# WAFC.net
KiCad netlist of a schematic drawn in Altium Designer
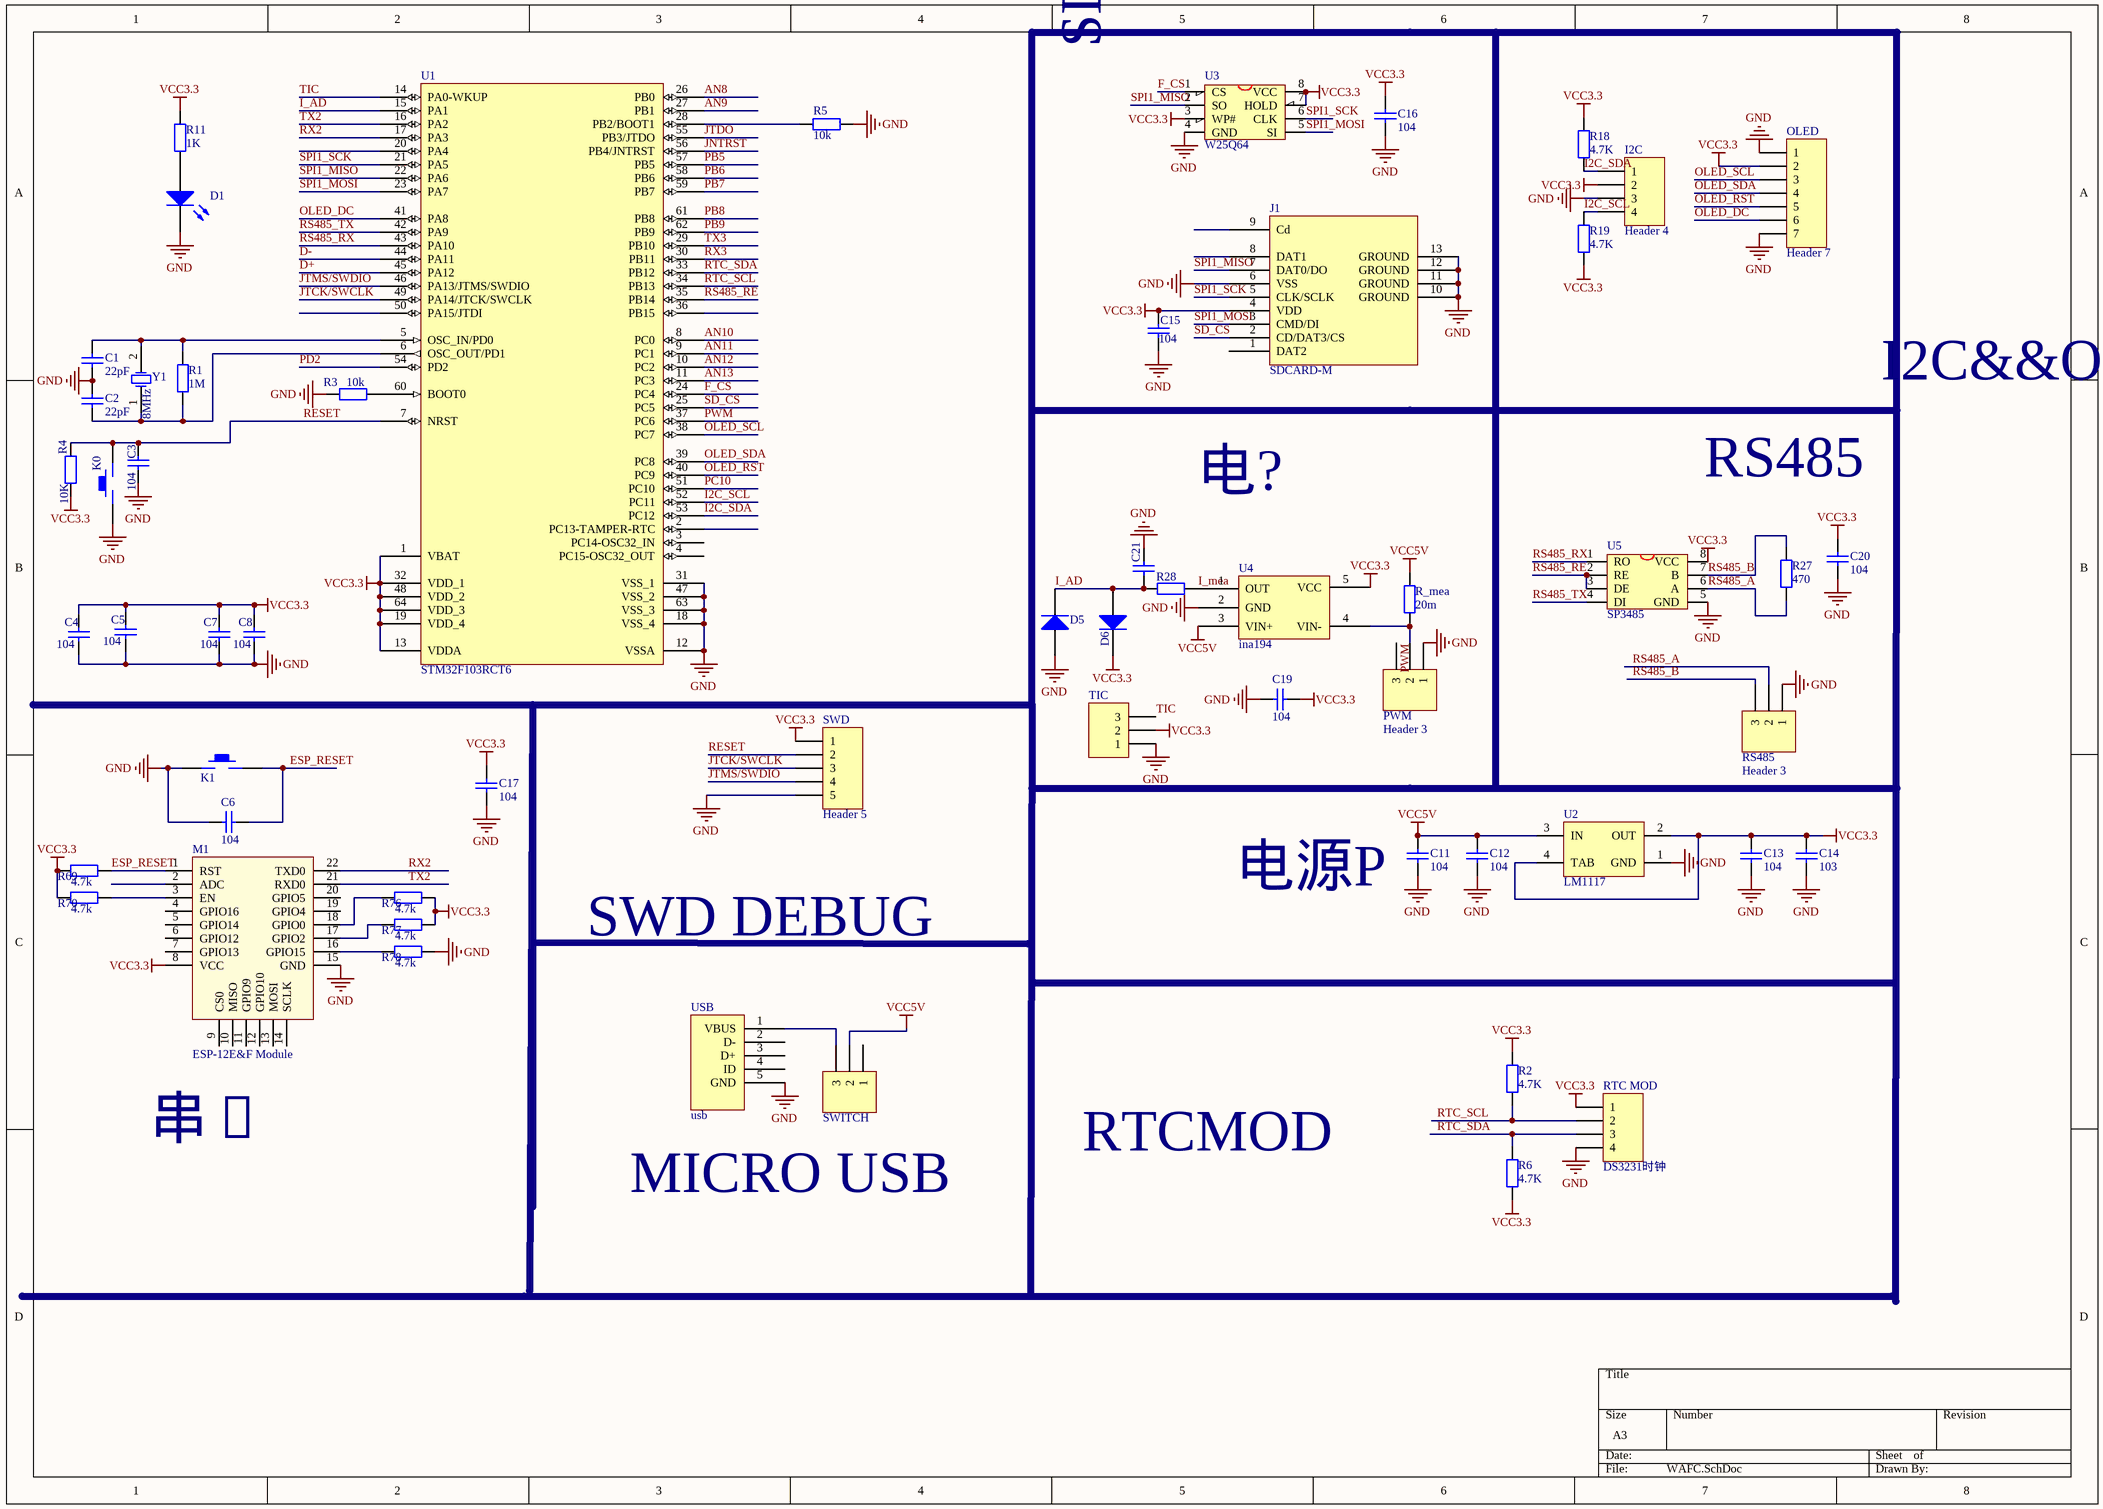
[diagram p0: WAFC.SchDoc]

(export (version "E")
  (design (tool "Eeschema 10.0.6"))
  (components
    (comp (ref "C1")
      (value "22pF")
      (footprint "0603")
      (description "Capacitor")
      (fields (field (name "Comment") "Cap") (field (name "PUBLISHER") "Altium Limited"))
      (libsource (lib "Miscellaneous Devices") (part "Cap"))
    )
    (comp (ref "C2")
      (value "22pF")
      (footprint "0603")
      (description "Capacitor")
      (fields (field (name "Comment") "Cap") (field (name "PUBLISHER") "Altium Limited"))
      (libsource (lib "Miscellaneous Devices") (part "Cap"))
    )
    (comp (ref "C3")
      (value "104")
      (footprint "0603")
      (description "Capacitor")
      (fields (field (name "Comment") "Cap") (field (name "PUBLISHER") "Altium Limited"))
      (libsource (lib "Miscellaneous Devices") (part "Cap"))
    )
    (comp (ref "C4")
      (value "104")
      (footprint "0603")
      (description "Capacitor")
      (fields (field (name "Comment") "Cap") (field (name "PUBLISHER") "Altium Limited"))
      (libsource (lib "Miscellaneous Devices") (part "Cap"))
    )
    (comp (ref "C5")
      (value "104")
      (footprint "0603")
      (description "Capacitor")
      (fields (field (name "Comment") "Cap") (field (name "PUBLISHER") "Altium Limited"))
      (libsource (lib "Miscellaneous Devices") (part "Cap"))
    )
    (comp (ref "C6")
      (value "104")
      (footprint "0603")
      (description "Capacitor")
      (fields (field (name "Comment") "Cap") (field (name "PUBLISHER") "Altium Limited"))
      (libsource (lib "Miscellaneous Devices") (part "Cap"))
    )
    (comp (ref "C7")
      (value "104")
      (footprint "0603")
      (description "Capacitor")
      (fields (field (name "Comment") "Cap") (field (name "PUBLISHER") "Altium Limited"))
      (libsource (lib "Miscellaneous Devices") (part "Cap"))
    )
    (comp (ref "C8")
      (value "104")
      (footprint "0603")
      (description "Capacitor")
      (fields (field (name "Comment") "Cap") (field (name "PUBLISHER") "Altium Limited"))
      (libsource (lib "Miscellaneous Devices") (part "Cap"))
    )
    (comp (ref "C11")
      (value "104")
      (footprint "0603")
      (description "Capacitor")
      (fields (field (name "Comment") "Cap") (field (name "PUBLISHER") "Altium Limited"))
      (libsource (lib "Miscellaneous Devices") (part "Cap"))
    )
    (comp (ref "C12")
      (value "104")
      (footprint "0603")
      (description "Capacitor")
      (fields (field (name "Comment") "Cap") (field (name "PUBLISHER") "Altium Limited"))
      (libsource (lib "Miscellaneous Devices") (part "Cap"))
    )
    (comp (ref "C13")
      (value "104")
      (footprint "0603")
      (description "Capacitor")
      (fields (field (name "Comment") "Cap") (field (name "PUBLISHER") "Altium Limited"))
      (libsource (lib "Miscellaneous Devices") (part "Cap"))
    )
    (comp (ref "C14")
      (value "103")
      (footprint "0603")
      (description "Capacitor")
      (fields (field (name "Comment") "Cap") (field (name "PUBLISHER") "Altium Limited"))
      (libsource (lib "Miscellaneous Devices") (part "Cap"))
    )
    (comp (ref "C15")
      (value "104")
      (footprint "0603")
      (description "Capacitor")
      (fields (field (name "Comment") "Cap") (field (name "PUBLISHER") "Altium Limited"))
      (libsource (lib "Miscellaneous Devices") (part "Cap"))
    )
    (comp (ref "C16")
      (value "104")
      (footprint "0603")
      (description "Capacitor")
      (fields (field (name "Comment") "Cap") (field (name "PUBLISHER") "Altium Limited"))
      (libsource (lib "Miscellaneous Devices") (part "Cap"))
    )
    (comp (ref "C17")
      (value "104")
      (footprint "0603")
      (description "Capacitor")
      (fields (field (name "Comment") "Cap") (field (name "PUBLISHER") "Altium Limited"))
      (libsource (lib "Miscellaneous Devices") (part "Cap"))
    )
    (comp (ref "C19")
      (value "104")
      (footprint "0603")
      (description "Capacitor")
      (fields (field (name "Comment") "Cap") (field (name "PUBLISHER") "Altium Limited"))
      (libsource (lib "Miscellaneous Devices") (part "Cap"))
    )
    (comp (ref "C20")
      (value "104")
      (footprint "0603")
      (description "Capacitor")
      (fields (field (name "Comment") "Cap") (field (name "PUBLISHER") "Altium Limited"))
      (libsource (lib "Miscellaneous Devices") (part "Cap"))
    )
    (comp (ref "C21")
      (value "Cap")
      (footprint "0603")
      (description "Capacitor")
      (fields (field (name "PUBLISHER") "Altium Limited"))
      (libsource (lib "Miscellaneous Devices") (part "Cap"))
    )
    (comp (ref "D1")
      (value "LED2")
      (footprint "0603")
      (description "Typical RED, GREEN, YELLOW, AMBER GaAs LED")
      (fields (field (name "PUBLISHER") "Altium Limited"))
      (libsource (lib "Miscellaneous Devices") (part "LED2"))
    )
    (comp (ref "D5")
      (value "SS14")
      (footprint "IN5819")
      (description "1 Amp General Purpose Rectifier")
      (fields (field (name "PUBLISHER") "Altium Limited"))
      (libsource (lib "Miscellaneous Devices") (part "Diode 1N4007"))
    )
    (comp (ref "D6")
      (value "SS14")
      (footprint "IN5819")
      (description "1 Amp General Purpose Rectifier")
      (fields (field (name "PUBLISHER") "Altium Limited"))
      (libsource (lib "Miscellaneous Devices") (part "Diode 1N4007"))
    )
    (comp (ref "I2C")
      (value "Header 4")
      (footprint "HDR1X4")
      (description "Header, 4-Pin")
      (fields (field (name "PUBLISHER") "Altium Limited"))
      (libsource (lib "Miscellaneous Connectors") (part "Header 4"))
    )
    (comp (ref "J1")
      (value "SDCARD-M")
      (footprint "SDCARD-M")
      (description "TF卡槽")
      (libsource (lib "MYLIB") (part "SDCARD-M"))
    )
    (comp (ref "K0") (value "K1") (footprint "sop2") (libsource (lib "") (part "KEY_1")))
    (comp (ref "K1") (value "K1") (footprint "sop2") (libsource (lib "MYLIB") (part "KEY")))
    (comp (ref "M1")
      (value "ESP-12E&F Module")
      (footprint "ESP-12E&F Module")
      (libsource (lib "ESP-12E&F Module") (part "ESP-12E&F Module"))
    )
    (comp (ref "OLED")
      (value "Header 7")
      (footprint "HDR1X7")
      (description "Header, 7-Pin")
      (fields (field (name "PUBLISHER") "Altium Limited"))
      (libsource (lib "Miscellaneous Connectors") (part "Header 7"))
    )
    (comp (ref "PWM")
      (value "Header 3")
      (footprint "HDR1X3")
      (description "Header, 3-Pin")
      (fields (field (name "PUBLISHER") "Altium Limited"))
      (libsource (lib "Miscellaneous Connectors") (part "Header 3"))
    )
    (comp (ref "R1")
      (value "1M")
      (footprint "0603")
      (description "Resistor")
      (fields (field (name "Comment") "Res2") (field (name "PUBLISHER") "Altium Limited"))
      (libsource (lib "Miscellaneous Devices") (part "Res2"))
    )
    (comp (ref "R2")
      (value "4.7K")
      (footprint "0603")
      (description "Resistor")
      (fields (field (name "Comment") "Res2") (field (name "PUBLISHER") "Altium Limited"))
      (libsource (lib "") (part "Res2_2"))
    )
    (comp (ref "R3")
      (value "10k")
      (footprint "0603")
      (description "Resistor")
      (fields (field (name "Comment") "Res2") (field (name "PUBLISHER") "Altium Limited"))
      (libsource (lib "") (part "Res2_1"))
    )
    (comp (ref "R4")
      (value "10K")
      (footprint "0603")
      (description "Resistor")
      (fields (field (name "Comment") "Res2") (field (name "PUBLISHER") "Altium Limited"))
      (libsource (lib "Miscellaneous Devices") (part "Res2"))
    )
    (comp (ref "R5")
      (value "10k")
      (footprint "0603")
      (description "Resistor")
      (fields (field (name "Comment") "Res2") (field (name "PUBLISHER") "Altium Limited"))
      (libsource (lib "") (part "Res2_1"))
    )
    (comp (ref "R6")
      (value "4.7K")
      (footprint "0603")
      (description "Resistor")
      (fields (field (name "Comment") "Res2") (field (name "PUBLISHER") "Altium Limited"))
      (libsource (lib "") (part "Res2_2"))
    )
    (comp (ref "R11")
      (value "1K")
      (footprint "0603")
      (description "Resistor")
      (fields (field (name "Comment") "Res2") (field (name "PUBLISHER") "Altium Limited"))
      (libsource (lib "Miscellaneous Devices") (part "Res2"))
    )
    (comp (ref "R18")
      (value "4.7K")
      (footprint "0603")
      (description "Resistor")
      (fields (field (name "Comment") "Res2") (field (name "PUBLISHER") "Altium Limited"))
      (libsource (lib "") (part "Res2_2"))
    )
    (comp (ref "R19")
      (value "4.7K")
      (footprint "0603")
      (description "Resistor")
      (fields (field (name "Comment") "Res2") (field (name "PUBLISHER") "Altium Limited"))
      (libsource (lib "") (part "Res2_2"))
    )
    (comp (ref "R27")
      (value "470")
      (footprint "0603")
      (description "Resistor")
      (fields (field (name "Comment") "Res2") (field (name "PUBLISHER") "Altium Limited"))
      (libsource (lib "") (part "Res2_2"))
    )
    (comp (ref "R28")
      (value "Res2")
      (footprint "0603")
      (description "Resistor")
      (fields (field (name "PUBLISHER") "Altium Limited"))
      (libsource (lib "") (part "Res2_3"))
    )
    (comp (ref "R69")
      (value "4.7k")
      (footprint "0603")
      (fields (field (name "Comment") "Res2"))
      (libsource (lib "S1") (part "RES"))
    )
    (comp (ref "R70")
      (value "4.7k")
      (footprint "0603")
      (fields (field (name "Comment") "Res2"))
      (libsource (lib "S1") (part "RES"))
    )
    (comp (ref "R76")
      (value "4.7k")
      (footprint "0603")
      (fields (field (name "Comment") "Res2"))
      (libsource (lib "S1") (part "RES"))
    )
    (comp (ref "R77")
      (value "4.7k")
      (footprint "0603")
      (fields (field (name "Comment") "Res2"))
      (libsource (lib "S1") (part "RES"))
    )
    (comp (ref "R78")
      (value "4.7k")
      (footprint "0603")
      (fields (field (name "Comment") "Res2"))
      (libsource (lib "S1") (part "RES"))
    )
    (comp (ref "RS485")
      (value "Header 3")
      (footprint "DZ3*3.5")
      (description "Header, 3-Pin")
      (fields (field (name "PUBLISHER") "Altium Limited"))
      (libsource (lib "Miscellaneous Connectors") (part "Header 3"))
    )
    (comp (ref "RTC MOD")
      (value "DS3231时钟")
      (footprint "HDR1X4")
      (description "Header, 4-Pin")
      (fields (field (name "PUBLISHER") "Altium Limited"))
      (libsource (lib "Miscellaneous Connectors") (part "Header 4"))
    )
    (comp (ref "R_mea")
      (value "20m")
      (footprint "0805")
      (description "Resistor")
      (fields (field (name "Comment") "Res2") (field (name "PUBLISHER") "Altium Limited"))
      (libsource (lib "Miscellaneous Devices") (part "Res2"))
    )
    (comp (ref "SWD")
      (value "Header 5")
      (footprint "HDR1X5")
      (description "Header, 5-Pin")
      (fields (field (name "PUBLISHER") "Altium Limited"))
      (libsource (lib "Miscellaneous Connectors") (part "Header 5"))
    )
    (comp (ref "SWITCH")
      (value "Header 3")
      (footprint "12D00")
      (description "Header, 3-Pin")
      (fields (field (name "PUBLISHER") "Altium Limited"))
      (libsource (lib "Miscellaneous Connectors") (part "Header 3"))
    )
    (comp (ref "TIC")
      (value "Header 3")
      (footprint "DZ3*3.5")
      (description "Header, 3-Pin")
      (fields (field (name "PUBLISHER") "Altium Limited"))
      (libsource (lib "") (part "Header 3_1"))
    )
    (comp (ref "U1")
      (value "STM32F103RCT6")
      (footprint "LQFP64")
      (description "STM32 ARM-based 32-bit MCU with 128 Kbytes Flash, 64-pin LQFP, Industrial Temperature")
      (fields (field (name "PUBLISHER") "Altium Limited"))
      (libsource (lib "MYLIB") (part "STM32F103RBT6"))
    )
    (comp (ref "U2")
      (value "LM1117")
      (footprint "MP04A_N")
      (description "800mA LDO")
      (fields
        (field (name "PARTNUMBER") "LM1117IMP-5.0")
        (field (name "MANUFACTURER") "National Semiconductor")
        (field (name "PUBLISHER") "Altium Limited")
      )
      (libsource (lib "MYLIB") (part "LM1117"))
    )
    (comp (ref "U3")
      (value "W25Q64")
      (footprint "SOIC-8")
      (description "W25X16;SST25VF016;MX25L1605")
      (libsource (lib "WARSHIP") (part "W25X16"))
    )
    (comp (ref "U4") (value "ina194") (footprint "ina194") (libsource (lib "MYLIB") (part "ina194")))
    (comp (ref "U5") (value "SP3485") (footprint "SOP-8") (libsource (lib "WARSHIP") (part "MAX3485")))
    (comp (ref "USB") (value "usb") (libsource (lib "xljc") (part "usb")))
    (comp (ref "Y1")
      (value "8MHz")
      (footprint "XTAL_US")
      (description "Crystal Oscillator")
      (fields (field (name "PUBLISHER") "Altium Limited"))
      (libsource (lib "WARSHIP") (part "XTAL"))
    )
  )
  (nets
    (net (code "1") (name "/AN8") (class "Default")
      (node (ref "U1") (pin "26") (pinfunction "PB0_26") (pintype "bidirectional"))
    )
    (net (code "2") (name "/AN9") (class "Default")
      (node (ref "U1") (pin "27") (pinfunction "PB1_27") (pintype "bidirectional"))
    )
    (net (code "3") (name "/AN10") (class "Default")
      (node (ref "U1") (pin "8") (pinfunction "PC0_8") (pintype "bidirectional"))
    )
    (net (code "4") (name "/AN11") (class "Default")
      (node (ref "U1") (pin "9") (pinfunction "PC1_9") (pintype "bidirectional"))
    )
    (net (code "5") (name "/AN12") (class "Default")
      (node (ref "U1") (pin "10") (pinfunction "PC2_10") (pintype "bidirectional"))
    )
    (net (code "6") (name "/AN13") (class "Default")
      (node (ref "U1") (pin "11") (pinfunction "PC3_11") (pintype "bidirectional"))
    )
    (net (code "7") (name "/D+") (class "Default")
      (node (ref "U1") (pin "45") (pinfunction "PA12_45") (pintype "bidirectional"))
    )
    (net (code "8") (name "/D-") (class "Default")
      (node (ref "U1") (pin "44") (pinfunction "PA11_44") (pintype "bidirectional"))
    )
    (net (code "9") (name "/ESP_RESET") (class "Default")
      (node (ref "C6") (pin "1") (pinfunction "1_1") (pintype "passive"))
      (node (ref "K1") (pin "2") (pinfunction "2_2") (pintype "passive"))
      (node (ref "M1") (pin "1") (pinfunction "RST_1") (pintype "passive"))
      (node (ref "R69") (pin "1") (pinfunction "1_1") (pintype "passive"))
    )
    (net (code "10") (name "/F_CS") (class "Default")
      (node (ref "U1") (pin "24") (pinfunction "PC4_24") (pintype "bidirectional"))
      (node (ref "U3") (pin "1") (pinfunction "CS_1") (pintype "passive"))
    )
    (net (code "11") (name "/I2C_SCL") (class "Default")
      (node (ref "I2C") (pin "4") (pinfunction "4_4") (pintype "passive"))
      (node (ref "R19") (pin "1") (pinfunction "1_1") (pintype "passive"))
      (node (ref "U1") (pin "52") (pinfunction "PC11_52") (pintype "bidirectional"))
    )
    (net (code "12") (name "/I2C_SDA") (class "Default")
      (node (ref "I2C") (pin "1") (pinfunction "1_1") (pintype "passive"))
      (node (ref "R18") (pin "2") (pinfunction "2_2") (pintype "passive"))
      (node (ref "U1") (pin "53") (pinfunction "PC12_53") (pintype "bidirectional"))
    )
    (net (code "13") (name "/I_AD") (class "Default")
      (node (ref "C21") (pin "1") (pinfunction "1_1") (pintype "passive"))
      (node (ref "D5") (pin "2") (pinfunction "K_2") (pintype "passive"))
      (node (ref "D6") (pin "1") (pinfunction "A_1") (pintype "passive"))
      (node (ref "R28") (pin "1") (pinfunction "1_1") (pintype "passive"))
      (node (ref "U1") (pin "15") (pinfunction "PA1_15") (pintype "bidirectional"))
    )
    (net (code "14") (name "/I_mea") (class "Default")
      (node (ref "R28") (pin "2") (pinfunction "2_2") (pintype "passive"))
      (node (ref "U4") (pin "1") (pinfunction "OUT_1") (pintype "passive"))
    )
    (net (code "15") (name "/JNTRST") (class "Default")
      (node (ref "U1") (pin "56") (pinfunction "PB4/JNTRST_56") (pintype "bidirectional"))
    )
    (net (code "16") (name "/JTCK{slash}SWCLK") (class "Default")
      (node (ref "SWD") (pin "3") (pinfunction "3_3") (pintype "passive"))
      (node (ref "U1") (pin "49") (pinfunction "PA14/JTCK/SWCLK_49") (pintype "bidirectional"))
    )
    (net (code "17") (name "/JTDO") (class "Default")
      (node (ref "U1") (pin "55") (pinfunction "PB3/JTDO_55") (pintype "bidirectional"))
    )
    (net (code "18") (name "/JTMS{slash}SWDIO") (class "Default")
      (node (ref "SWD") (pin "4") (pinfunction "4_4") (pintype "passive"))
      (node (ref "U1") (pin "46") (pinfunction "PA13/JTMS/SWDIO_46") (pintype "bidirectional"))
    )
    (net (code "19") (name "/OLED_DC") (class "Default")
      (node (ref "OLED") (pin "6") (pinfunction "6_6") (pintype "passive"))
      (node (ref "U1") (pin "41") (pinfunction "PA8_41") (pintype "bidirectional"))
    )
    (net (code "20") (name "/OLED_RST") (class "Default")
      (node (ref "OLED") (pin "5") (pinfunction "5_5") (pintype "passive"))
      (node (ref "U1") (pin "40") (pinfunction "PC9_40") (pintype "bidirectional"))
    )
    (net (code "21") (name "/OLED_SCL") (class "Default")
      (node (ref "OLED") (pin "3") (pinfunction "3_3") (pintype "passive"))
      (node (ref "U1") (pin "38") (pinfunction "PC7_38") (pintype "bidirectional"))
    )
    (net (code "22") (name "/OLED_SDA") (class "Default")
      (node (ref "OLED") (pin "4") (pinfunction "4_4") (pintype "passive"))
      (node (ref "U1") (pin "39") (pinfunction "PC8_39") (pintype "bidirectional"))
    )
    (net (code "23") (name "/PB5") (class "Default")
      (node (ref "U1") (pin "57") (pinfunction "PB5_57") (pintype "bidirectional"))
    )
    (net (code "24") (name "/PB6") (class "Default")
      (node (ref "U1") (pin "58") (pinfunction "PB6_58") (pintype "bidirectional"))
    )
    (net (code "25") (name "/PB7") (class "Default")
      (node (ref "U1") (pin "59") (pinfunction "PB7_59") (pintype "bidirectional"))
    )
    (net (code "26") (name "/PB8") (class "Default")
      (node (ref "U1") (pin "61") (pinfunction "PB8_61") (pintype "bidirectional"))
    )
    (net (code "27") (name "/PB9") (class "Default")
      (node (ref "U1") (pin "62") (pinfunction "PB9_62") (pintype "bidirectional"))
    )
    (net (code "28") (name "/PC10") (class "Default")
      (node (ref "U1") (pin "51") (pinfunction "PC10_51") (pintype "bidirectional"))
    )
    (net (code "29") (name "/PD2") (class "Default")
      (node (ref "U1") (pin "54") (pinfunction "PD2_54") (pintype "bidirectional"))
    )
    (net (code "30") (name "/PWM") (class "Default")
      (node (ref "PWM") (pin "3") (pinfunction "3_3") (pintype "passive"))
      (node (ref "U1") (pin "37") (pinfunction "PC6_37") (pintype "bidirectional"))
    )
    (net (code "31") (name "/RESET") (class "Default")
      (node (ref "C3") (pin "2") (pinfunction "2_2") (pintype "passive"))
      (node (ref "K0") (pin "2") (pinfunction "2_2") (pintype "passive"))
      (node (ref "R4") (pin "2") (pinfunction "2_2") (pintype "passive"))
      (node (ref "SWD") (pin "2") (pinfunction "2_2") (pintype "passive"))
      (node (ref "U1") (pin "7") (pinfunction "NRST_7") (pintype "bidirectional"))
    )
    (net (code "32") (name "/RS485_A") (class "Default")
      (node (ref "R27") (pin "2") (pinfunction "2_2") (pintype "passive"))
      (node (ref "RS485") (pin "2") (pinfunction "2_2") (pintype "passive"))
      (node (ref "U5") (pin "6") (pinfunction "A_6") (pintype "passive"))
    )
    (net (code "33") (name "/RS485_B") (class "Default")
      (node (ref "R27") (pin "1") (pinfunction "1_1") (pintype "passive"))
      (node (ref "RS485") (pin "3") (pinfunction "3_3") (pintype "passive"))
      (node (ref "U5") (pin "7") (pinfunction "B_7") (pintype "passive"))
    )
    (net (code "34") (name "/RS485_RE") (class "Default")
      (node (ref "U1") (pin "35") (pinfunction "PB14_35") (pintype "bidirectional"))
      (node (ref "U5") (pin "2") (pinfunction "RE_2") (pintype "passive"))
      (node (ref "U5") (pin "3") (pinfunction "DE_3") (pintype "passive"))
    )
    (net (code "35") (name "/RS485_RX") (class "Default")
      (node (ref "U1") (pin "43") (pinfunction "PA10_43") (pintype "bidirectional"))
      (node (ref "U5") (pin "1") (pinfunction "RO_1") (pintype "passive"))
    )
    (net (code "36") (name "/RS485_TX") (class "Default")
      (node (ref "U1") (pin "42") (pinfunction "PA9_42") (pintype "bidirectional"))
      (node (ref "U5") (pin "4") (pinfunction "DI_4") (pintype "passive"))
    )
    (net (code "37") (name "/RTC_SCL") (class "Default")
      (node (ref "R2") (pin "2") (pinfunction "2_2") (pintype "passive"))
      (node (ref "RTC MOD") (pin "2") (pinfunction "2_2") (pintype "passive"))
      (node (ref "U1") (pin "34") (pinfunction "PB13_34") (pintype "bidirectional"))
    )
    (net (code "38") (name "/RTC_SDA") (class "Default")
      (node (ref "R6") (pin "1") (pinfunction "1_1") (pintype "passive"))
      (node (ref "RTC MOD") (pin "3") (pinfunction "3_3") (pintype "passive"))
      (node (ref "U1") (pin "33") (pinfunction "PB12_33") (pintype "bidirectional"))
    )
    (net (code "39") (name "/RX2") (class "Default")
      (node (ref "M1") (pin "22") (pinfunction "TXD0_22") (pintype "passive"))
      (node (ref "U1") (pin "17") (pinfunction "PA3_17") (pintype "bidirectional"))
    )
    (net (code "40") (name "/RX3") (class "Default")
      (node (ref "U1") (pin "30") (pinfunction "PB11_30") (pintype "bidirectional"))
    )
    (net (code "41") (name "/SD_CS") (class "Default")
      (node (ref "J1") (pin "2") (pinfunction "CD/DAT3/CS_2") (pintype "passive"))
      (node (ref "U1") (pin "25") (pinfunction "PC5_25") (pintype "bidirectional"))
    )
    (net (code "42") (name "/SPI1_MISO") (class "Default")
      (node (ref "J1") (pin "7") (pinfunction "DAT0/DO_7") (pintype "passive"))
      (node (ref "U1") (pin "22") (pinfunction "PA6_22") (pintype "bidirectional"))
      (node (ref "U3") (pin "2") (pinfunction "SO_2") (pintype "passive"))
    )
    (net (code "43") (name "/SPI1_MOSI") (class "Default")
      (node (ref "J1") (pin "3") (pinfunction "CMD/DI_3") (pintype "passive"))
      (node (ref "U1") (pin "23") (pinfunction "PA7_23") (pintype "bidirectional"))
      (node (ref "U3") (pin "5") (pinfunction "SI_5") (pintype "passive"))
    )
    (net (code "44") (name "/SPI1_SCK") (class "Default")
      (node (ref "J1") (pin "5") (pinfunction "CLK/SCLK_5") (pintype "passive"))
      (node (ref "U1") (pin "21") (pinfunction "PA5_21") (pintype "bidirectional"))
      (node (ref "U3") (pin "6") (pinfunction "CLK_6") (pintype "passive"))
    )
    (net (code "45") (name "/TIC") (class "Default")
      (node (ref "TIC") (pin "3") (pinfunction "3_3") (pintype "passive"))
      (node (ref "U1") (pin "14") (pinfunction "PA0-WKUP_14") (pintype "bidirectional"))
    )
    (net (code "46") (name "/TX2") (class "Default")
      (node (ref "M1") (pin "21") (pinfunction "RXD0_21") (pintype "passive"))
      (node (ref "U1") (pin "16") (pinfunction "PA2_16") (pintype "bidirectional"))
    )
    (net (code "47") (name "/TX3") (class "Default")
      (node (ref "U1") (pin "29") (pinfunction "PB10_29") (pintype "bidirectional"))
    )
    (net (code "48") (name "GND") (class "Default")
      (node (ref "C1") (pin "1") (pinfunction "1_1") (pintype "passive"))
      (node (ref "C11") (pin "1") (pinfunction "1_1") (pintype "passive"))
      (node (ref "C12") (pin "1") (pinfunction "1_1") (pintype "passive"))
      (node (ref "C13") (pin "1") (pinfunction "1_1") (pintype "passive"))
      (node (ref "C14") (pin "1") (pinfunction "1_1") (pintype "passive"))
      (node (ref "C15") (pin "1") (pinfunction "1_1") (pintype "passive"))
      (node (ref "C16") (pin "1") (pinfunction "1_1") (pintype "passive"))
      (node (ref "C17") (pin "1") (pinfunction "1_1") (pintype "passive"))
      (node (ref "C19") (pin "1") (pinfunction "1_1") (pintype "passive"))
      (node (ref "C2") (pin "2") (pinfunction "2_2") (pintype "passive"))
      (node (ref "C20") (pin "1") (pinfunction "1_1") (pintype "passive"))
      (node (ref "C21") (pin "2") (pinfunction "2_2") (pintype "passive"))
      (node (ref "C3") (pin "1") (pinfunction "1_1") (pintype "passive"))
      (node (ref "C4") (pin "2") (pinfunction "2_2") (pintype "passive"))
      (node (ref "C5") (pin "2") (pinfunction "2_2") (pintype "passive"))
      (node (ref "C6") (pin "2") (pinfunction "2_2") (pintype "passive"))
      (node (ref "C7") (pin "2") (pinfunction "2_2") (pintype "passive"))
      (node (ref "C8") (pin "2") (pinfunction "2_2") (pintype "passive"))
      (node (ref "D1") (pin "2") (pinfunction "K_2") (pintype "passive"))
      (node (ref "D5") (pin "1") (pinfunction "A_1") (pintype "passive"))
      (node (ref "I2C") (pin "3") (pinfunction "3_3") (pintype "passive"))
      (node (ref "J1") (pin "10") (pinfunction "GROUND_10") (pintype "passive"))
      (node (ref "J1") (pin "11") (pinfunction "GROUND_11") (pintype "passive"))
      (node (ref "J1") (pin "12") (pinfunction "GROUND_12") (pintype "passive"))
      (node (ref "J1") (pin "13") (pinfunction "GROUND_13") (pintype "passive"))
      (node (ref "J1") (pin "6") (pinfunction "VSS_6") (pintype "passive"))
      (node (ref "K0") (pin "1") (pinfunction "1_1") (pintype "passive"))
      (node (ref "K1") (pin "1") (pinfunction "1_1") (pintype "passive"))
      (node (ref "M1") (pin "15") (pinfunction "GND_15") (pintype "passive"))
      (node (ref "OLED") (pin "1") (pinfunction "1_1") (pintype "passive"))
      (node (ref "OLED") (pin "7") (pinfunction "7_7") (pintype "passive"))
      (node (ref "PWM") (pin "1") (pinfunction "1_1") (pintype "passive"))
      (node (ref "R3") (pin "2") (pinfunction "2_2") (pintype "passive"))
      (node (ref "R5") (pin "1") (pinfunction "1_1") (pintype "passive"))
      (node (ref "R78") (pin "1") (pinfunction "1_1") (pintype "passive"))
      (node (ref "RS485") (pin "1") (pinfunction "1_1") (pintype "passive"))
      (node (ref "RTC MOD") (pin "4") (pinfunction "4_4") (pintype "passive"))
      (node (ref "SWD") (pin "5") (pinfunction "5_5") (pintype "passive"))
      (node (ref "TIC") (pin "1") (pinfunction "1_1") (pintype "passive"))
      (node (ref "U1") (pin "12") (pinfunction "VSSA_12") (pintype "power_in"))
      (node (ref "U1") (pin "18") (pinfunction "VSS_4_18") (pintype "power_in"))
      (node (ref "U1") (pin "31") (pinfunction "VSS_1_31") (pintype "power_in"))
      (node (ref "U1") (pin "47") (pinfunction "VSS_2_47") (pintype "power_in"))
      (node (ref "U1") (pin "63") (pinfunction "VSS_3_63") (pintype "power_in"))
      (node (ref "U2") (pin "1") (pinfunction "GND_1") (pintype "power_in"))
      (node (ref "U3") (pin "4") (pinfunction "GND_4") (pintype "passive"))
      (node (ref "U4") (pin "2") (pinfunction "GND_2") (pintype "passive"))
      (node (ref "U5") (pin "5") (pinfunction "GND_5") (pintype "passive"))
      (node (ref "USB") (pin "5") (pinfunction "GND_5") (pintype "passive"))
    )
    (net (code "49") (name "Net-(D1-A)") (class "Default")
      (node (ref "D1") (pin "1") (pinfunction "A_1") (pintype "passive"))
      (node (ref "R11") (pin "1") (pinfunction "1_1") (pintype "passive"))
    )
    (net (code "50") (name "Net-(M1-EN)") (class "Default")
      (node (ref "M1") (pin "3") (pinfunction "EN_3") (pintype "passive"))
      (node (ref "R70") (pin "1") (pinfunction "1_1") (pintype "passive"))
    )
    (net (code "51") (name "Net-(M1-GPIO0)") (class "Default")
      (node (ref "M1") (pin "18") (pinfunction "GPIO0_18") (pintype "passive"))
      (node (ref "R76") (pin "2") (pinfunction "2_2") (pintype "passive"))
    )
    (net (code "52") (name "Net-(M1-GPIO2)") (class "Default")
      (node (ref "M1") (pin "17") (pinfunction "GPIO2_17") (pintype "passive"))
      (node (ref "R77") (pin "2") (pinfunction "2_2") (pintype "passive"))
    )
    (net (code "53") (name "Net-(M1-GPIO15)") (class "Default")
      (node (ref "M1") (pin "16") (pinfunction "GPIO15_16") (pintype "passive"))
      (node (ref "R78") (pin "2") (pinfunction "2_2") (pintype "passive"))
    )
    (net (code "54") (name "Net-(U1-BOOT0)") (class "Default")
      (node (ref "R3") (pin "1") (pinfunction "1_1") (pintype "passive"))
      (node (ref "U1") (pin "60") (pinfunction "BOOT0_60") (pintype "input"))
    )
    (net (code "55") (name "Net-(U1-OSC_IN{slash}PD0)") (class "Default")
      (node (ref "C1") (pin "2") (pinfunction "2_2") (pintype "passive"))
      (node (ref "R1") (pin "2") (pinfunction "2_2") (pintype "passive"))
      (node (ref "U1") (pin "5") (pinfunction "OSC_IN/PD0_5") (pintype "input"))
      (node (ref "Y1") (pin "2") (pinfunction "OSC2_2") (pintype "passive"))
    )
    (net (code "56") (name "Net-(U1-OSC_OUT{slash}PD1)") (class "Default")
      (node (ref "C2") (pin "1") (pinfunction "1_1") (pintype "passive"))
      (node (ref "R1") (pin "1") (pinfunction "1_1") (pintype "passive"))
      (node (ref "U1") (pin "6") (pinfunction "OSC_OUT/PD1_6") (pintype "output"))
      (node (ref "Y1") (pin "1") (pinfunction "OSC1_1") (pintype "passive"))
    )
    (net (code "57") (name "Net-(U1-PB2{slash}BOOT1)") (class "Default")
      (node (ref "R5") (pin "2") (pinfunction "2_2") (pintype "passive"))
      (node (ref "U1") (pin "28") (pinfunction "PB2/BOOT1_28") (pintype "bidirectional"))
    )
    (net (code "58") (name "Net-(U4-VIN-)") (class "Default")
      (node (ref "PWM") (pin "2") (pinfunction "2_2") (pintype "passive"))
      (node (ref "R_mea") (pin "1") (pinfunction "1_1") (pintype "passive"))
      (node (ref "U4") (pin "4") (pinfunction "VIN-_4") (pintype "passive"))
    )
    (net (code "59") (name "Net-(USB-VBUS)") (class "Default")
      (node (ref "SWITCH") (pin "3") (pinfunction "3_3") (pintype "passive"))
      (node (ref "USB") (pin "1") (pinfunction "VBUS_1") (pintype "passive"))
    )
    (net (code "60") (name "VCC3.3") (class "Default")
      (node (ref "C13") (pin "2") (pinfunction "2_2") (pintype "passive"))
      (node (ref "C14") (pin "2") (pinfunction "2_2") (pintype "passive"))
      (node (ref "C15") (pin "2") (pinfunction "2_2") (pintype "passive"))
      (node (ref "C16") (pin "2") (pinfunction "2_2") (pintype "passive"))
      (node (ref "C17") (pin "2") (pinfunction "2_2") (pintype "passive"))
      (node (ref "C19") (pin "2") (pinfunction "2_2") (pintype "passive"))
      (node (ref "C20") (pin "2") (pinfunction "2_2") (pintype "passive"))
      (node (ref "C4") (pin "1") (pinfunction "1_1") (pintype "passive"))
      (node (ref "C5") (pin "1") (pinfunction "1_1") (pintype "passive"))
      (node (ref "C7") (pin "1") (pinfunction "1_1") (pintype "passive"))
      (node (ref "C8") (pin "1") (pinfunction "1_1") (pintype "passive"))
      (node (ref "D6") (pin "2") (pinfunction "K_2") (pintype "passive"))
      (node (ref "I2C") (pin "2") (pinfunction "2_2") (pintype "passive"))
      (node (ref "J1") (pin "4") (pinfunction "VDD_4") (pintype "passive"))
      (node (ref "M1") (pin "8") (pinfunction "VCC_8") (pintype "passive"))
      (node (ref "OLED") (pin "2") (pinfunction "2_2") (pintype "passive"))
      (node (ref "R11") (pin "2") (pinfunction "2_2") (pintype "passive"))
      (node (ref "R18") (pin "1") (pinfunction "1_1") (pintype "passive"))
      (node (ref "R19") (pin "2") (pinfunction "2_2") (pintype "passive"))
      (node (ref "R2") (pin "1") (pinfunction "1_1") (pintype "passive"))
      (node (ref "R4") (pin "1") (pinfunction "1_1") (pintype "passive"))
      (node (ref "R6") (pin "2") (pinfunction "2_2") (pintype "passive"))
      (node (ref "R69") (pin "2") (pinfunction "2_2") (pintype "passive"))
      (node (ref "R70") (pin "2") (pinfunction "2_2") (pintype "passive"))
      (node (ref "R76") (pin "1") (pinfunction "1_1") (pintype "passive"))
      (node (ref "R77") (pin "1") (pinfunction "1_1") (pintype "passive"))
      (node (ref "RTC MOD") (pin "1") (pinfunction "1_1") (pintype "passive"))
      (node (ref "SWD") (pin "1") (pinfunction "1_1") (pintype "passive"))
      (node (ref "TIC") (pin "2") (pinfunction "2_2") (pintype "passive"))
      (node (ref "U1") (pin "1") (pinfunction "VBAT_1") (pintype "power_in"))
      (node (ref "U1") (pin "13") (pinfunction "VDDA_13") (pintype "power_in"))
      (node (ref "U1") (pin "19") (pinfunction "VDD_4_19") (pintype "power_in"))
      (node (ref "U1") (pin "32") (pinfunction "VDD_1_32") (pintype "power_in"))
      (node (ref "U1") (pin "48") (pinfunction "VDD_2_48") (pintype "power_in"))
      (node (ref "U1") (pin "64") (pinfunction "VDD_3_64") (pintype "power_in"))
      (node (ref "U2") (pin "2") (pinfunction "OUT_2") (pintype "power_in"))
      (node (ref "U2") (pin "4") (pinfunction "TAB_4") (pintype "power_in"))
      (node (ref "U3") (pin "3") (pinfunction "WP#_3") (pintype "passive"))
      (node (ref "U3") (pin "7") (pinfunction "HOLD_7") (pintype "passive"))
      (node (ref "U3") (pin "8") (pinfunction "VCC_8") (pintype "passive"))
      (node (ref "U4") (pin "5") (pinfunction "VCC_5") (pintype "passive"))
      (node (ref "U5") (pin "8") (pinfunction "VCC_8") (pintype "passive"))
    )
    (net (code "61") (name "VCC5V") (class "Default")
      (node (ref "C11") (pin "2") (pinfunction "2_2") (pintype "passive"))
      (node (ref "C12") (pin "2") (pinfunction "2_2") (pintype "passive"))
      (node (ref "R_mea") (pin "2") (pinfunction "2_2") (pintype "passive"))
      (node (ref "SWITCH") (pin "2") (pinfunction "2_2") (pintype "passive"))
      (node (ref "U2") (pin "3") (pinfunction "IN_3") (pintype "power_in"))
      (node (ref "U4") (pin "3") (pinfunction "VIN+_3") (pintype "passive"))
    )
    (net (code "62") (name "unconnected-(J1-Cd-Pad9)") (class "Default")
      (node (ref "J1") (pin "9") (pinfunction "Cd_9") (pintype "passive"))
    )
    (net (code "63") (name "unconnected-(J1-DAT1-Pad8)") (class "Default")
      (node (ref "J1") (pin "8") (pinfunction "DAT1_8") (pintype "passive"))
    )
    (net (code "64") (name "unconnected-(J1-DAT2-Pad1)") (class "Default")
      (node (ref "J1") (pin "1") (pinfunction "DAT2_1") (pintype "passive"))
    )
    (net (code "65") (name "unconnected-(M1-ADC-Pad2)") (class "Default")
      (node (ref "M1") (pin "2") (pinfunction "ADC_2") (pintype "passive"))
    )
    (net (code "66") (name "unconnected-(M1-CS0-Pad9)") (class "Default")
      (node (ref "M1") (pin "9") (pinfunction "CS0_9") (pintype "passive"))
    )
    (net (code "67") (name "unconnected-(M1-GPIO4-Pad19)") (class "Default")
      (node (ref "M1") (pin "19") (pinfunction "GPIO4_19") (pintype "passive"))
    )
    (net (code "68") (name "unconnected-(M1-GPIO5-Pad20)") (class "Default")
      (node (ref "M1") (pin "20") (pinfunction "GPIO5_20") (pintype "passive"))
    )
    (net (code "69") (name "unconnected-(M1-GPIO9-Pad11)") (class "Default")
      (node (ref "M1") (pin "11") (pinfunction "GPIO9_11") (pintype "passive"))
    )
    (net (code "70") (name "unconnected-(M1-GPIO10-Pad12)") (class "Default")
      (node (ref "M1") (pin "12") (pinfunction "GPIO10_12") (pintype "passive"))
    )
    (net (code "71") (name "unconnected-(M1-GPIO12-Pad6)") (class "Default")
      (node (ref "M1") (pin "6") (pinfunction "GPIO12_6") (pintype "passive"))
    )
    (net (code "72") (name "unconnected-(M1-GPIO13-Pad7)") (class "Default")
      (node (ref "M1") (pin "7") (pinfunction "GPIO13_7") (pintype "passive"))
    )
    (net (code "73") (name "unconnected-(M1-GPIO14-Pad5)") (class "Default")
      (node (ref "M1") (pin "5") (pinfunction "GPIO14_5") (pintype "passive"))
    )
    (net (code "74") (name "unconnected-(M1-GPIO16-Pad4)") (class "Default")
      (node (ref "M1") (pin "4") (pinfunction "GPIO16_4") (pintype "passive"))
    )
    (net (code "75") (name "unconnected-(M1-MISO-Pad10)") (class "Default")
      (node (ref "M1") (pin "10") (pinfunction "MISO_10") (pintype "passive"))
    )
    (net (code "76") (name "unconnected-(M1-MOSI-Pad13)") (class "Default")
      (node (ref "M1") (pin "13") (pinfunction "MOSI_13") (pintype "passive"))
    )
    (net (code "77") (name "unconnected-(M1-SCLK-Pad14)") (class "Default")
      (node (ref "M1") (pin "14") (pinfunction "SCLK_14") (pintype "passive"))
    )
    (net (code "78") (name "unconnected-(SWITCH-Pad1)") (class "Default")
      (node (ref "SWITCH") (pin "1") (pinfunction "1_1") (pintype "passive"))
    )
    (net (code "79") (name "unconnected-(U1-PA4-Pad20)") (class "Default")
      (node (ref "U1") (pin "20") (pinfunction "PA4_20") (pintype "bidirectional"))
    )
    (net (code "80") (name "unconnected-(U1-PA15{slash}JTDI-Pad50)") (class "Default")
      (node (ref "U1") (pin "50") (pinfunction "PA15/JTDI_50") (pintype "bidirectional"))
    )
    (net (code "81") (name "unconnected-(U1-PB15-Pad36)") (class "Default")
      (node (ref "U1") (pin "36") (pinfunction "PB15_36") (pintype "bidirectional"))
    )
    (net (code "82") (name "unconnected-(U1-PC13-TAMPER-RTC-Pad2)") (class "Default")
      (node (ref "U1") (pin "2") (pinfunction "PC13-TAMPER-RTC_2") (pintype "bidirectional"))
    )
    (net (code "83") (name "unconnected-(U1-PC14-OSC32_IN-Pad3)") (class "Default")
      (node (ref "U1") (pin "3") (pinfunction "PC14-OSC32_IN_3") (pintype "bidirectional"))
    )
    (net (code "84") (name "unconnected-(U1-PC15-OSC32_OUT-Pad4)") (class "Default")
      (node (ref "U1") (pin "4") (pinfunction "PC15-OSC32_OUT_4") (pintype "bidirectional"))
    )
    (net (code "85") (name "unconnected-(USB-D+-Pad3)") (class "Default")
      (node (ref "USB") (pin "3") (pinfunction "D+_3") (pintype "passive"))
    )
    (net (code "86") (name "unconnected-(USB-D--Pad2)") (class "Default")
      (node (ref "USB") (pin "2") (pinfunction "D-_2") (pintype "passive"))
    )
    (net (code "87") (name "unconnected-(USB-ID-Pad4)") (class "Default")
      (node (ref "USB") (pin "4") (pinfunction "ID_4") (pintype "passive"))
    )
  )
)
